# Schematic_drone.net
KiCad netlist of a schematic drawn in EasyEDA
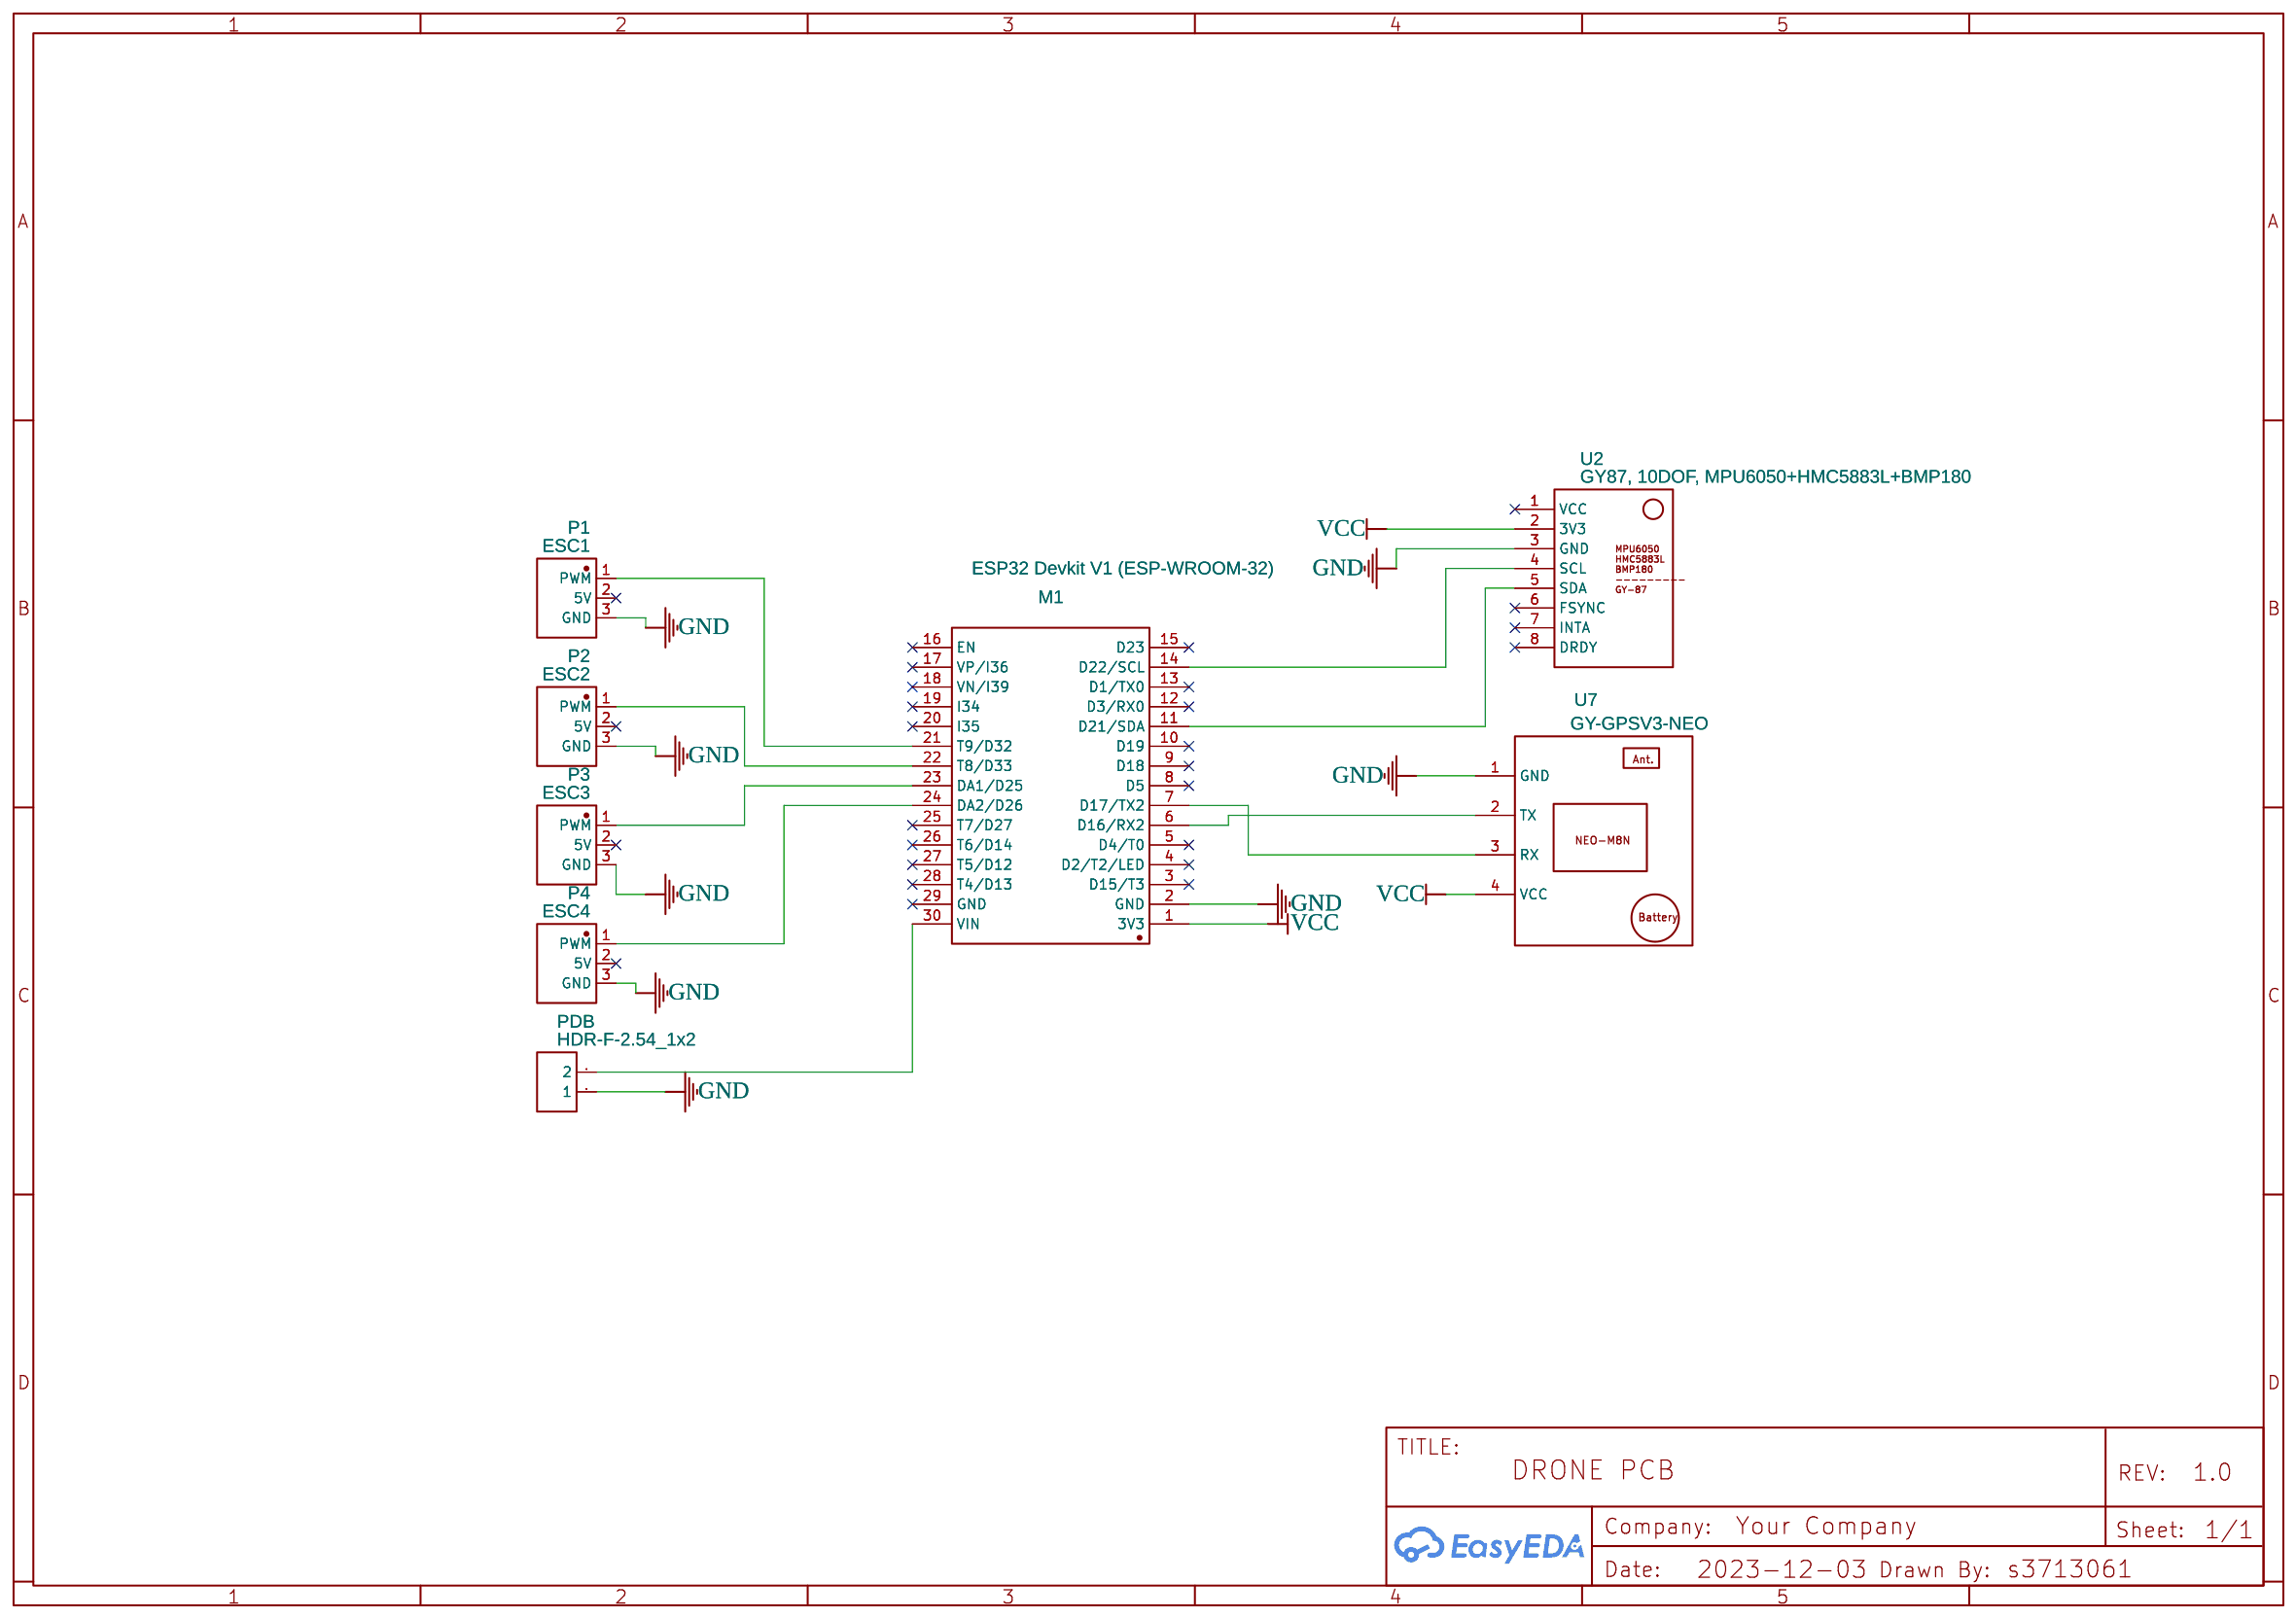
[diagram p0: schematic sheet]

(export (version "E")
  (design (tool "Eeschema 10.0.6"))
  (components
    (comp (ref "M1")
      (value "ESP32 Devkit V1 (ESP-WROOM-32)")
      (libsource (lib "") (part "S.Mod.ESP32_DOIT_V1 copy"))
    )
    (comp (ref "P1")
      (value "ESC1")
      (fields (field (name "Manufacturer") "Header2.54mm"))
      (libsource (lib "") (part "ESCPort"))
    )
    (comp (ref "P2")
      (value "ESC2")
      (fields (field (name "Manufacturer") "Header2.54mm"))
      (libsource (lib "") (part "ESCPort"))
    )
    (comp (ref "P3")
      (value "ESC3")
      (fields (field (name "Manufacturer") "Header2.54mm"))
      (libsource (lib "") (part "ESCPort"))
    )
    (comp (ref "P4")
      (value "ESC4")
      (fields (field (name "Manufacturer") "Header2.54mm"))
      (libsource (lib "") (part "ESCPort"))
    )
    (comp (ref "PDB")
      (value "HDR-F-2.54_1x2")
      (fields (field (name "Manufacturer") "Header2.54mm"))
      (libsource (lib "") (part "HDR-F-2.54_1x2"))
    )
    (comp (ref "U2")
      (value "GY87, 10DOF, MPU6050+HMC5883L+BMP180")
      (libsource (lib "") (part "GY87, 10DOF, MPU6050+HMC5883L+BMP180"))
    )
    (comp (ref "U7") (value "GY-GPSV3-NEO") (libsource (lib "") (part "GY-GPSV3-NEO COPY COPY")))
  )
  (nets
    (net (code "1") (name "GND") (class "Default")
      (node (ref "M1") (pin "2") (pinfunction "GND_2") (pintype "passive"))
      (node (ref "P1") (pin "3") (pinfunction "GND_3") (pintype "unspecified"))
      (node (ref "P2") (pin "3") (pinfunction "GND_3") (pintype "unspecified"))
      (node (ref "P3") (pin "3") (pinfunction "GND_3") (pintype "unspecified"))
      (node (ref "P4") (pin "3") (pinfunction "GND_3") (pintype "unspecified"))
      (node (ref "PDB") (pin "1") (pinfunction "1_1") (pintype "input"))
      (node (ref "U2") (pin "3") (pinfunction "GND_3") (pintype "unspecified"))
      (node (ref "U7") (pin "1") (pinfunction "GND_1") (pintype "unspecified"))
    )
    (net (code "2") (name "Net-(M1-D16{slash}RX2)") (class "Default")
      (node (ref "M1") (pin "6") (pinfunction "D16/RX2_6") (pintype "unspecified"))
      (node (ref "U7") (pin "2") (pinfunction "TX_2") (pintype "unspecified"))
    )
    (net (code "3") (name "Net-(M1-D17{slash}TX2)") (class "Default")
      (node (ref "M1") (pin "7") (pinfunction "D17/TX2_7") (pintype "unspecified"))
      (node (ref "U7") (pin "3") (pinfunction "RX_3") (pintype "unspecified"))
    )
    (net (code "4") (name "Net-(M1-D21{slash}SDA)") (class "Default")
      (node (ref "M1") (pin "11") (pinfunction "D21/SDA_11") (pintype "unspecified"))
      (node (ref "U2") (pin "5") (pinfunction "SDA_5") (pintype "unspecified"))
    )
    (net (code "5") (name "Net-(M1-D22{slash}SCL)") (class "Default")
      (node (ref "M1") (pin "14") (pinfunction "D22/SCL_14") (pintype "unspecified"))
      (node (ref "U2") (pin "4") (pinfunction "SCL_4") (pintype "unspecified"))
    )
    (net (code "6") (name "Net-(M1-DA1{slash}D25)") (class "Default")
      (node (ref "M1") (pin "23") (pinfunction "DA1/D25_23") (pintype "unspecified"))
      (node (ref "P3") (pin "1") (pinfunction "PWM_1") (pintype "unspecified"))
    )
    (net (code "7") (name "Net-(M1-DA2{slash}D26)") (class "Default")
      (node (ref "M1") (pin "24") (pinfunction "DA2/D26_24") (pintype "unspecified"))
      (node (ref "P4") (pin "1") (pinfunction "PWM_1") (pintype "unspecified"))
    )
    (net (code "8") (name "Net-(M1-T8{slash}D33)") (class "Default")
      (node (ref "M1") (pin "22") (pinfunction "T8/D33_22") (pintype "unspecified"))
      (node (ref "P2") (pin "1") (pinfunction "PWM_1") (pintype "unspecified"))
    )
    (net (code "9") (name "Net-(M1-T9{slash}D32)") (class "Default")
      (node (ref "M1") (pin "21") (pinfunction "T9/D32_21") (pintype "unspecified"))
      (node (ref "P1") (pin "1") (pinfunction "PWM_1") (pintype "unspecified"))
    )
    (net (code "10") (name "Net-(M1-VIN)") (class "Default")
      (node (ref "M1") (pin "30") (pinfunction "VIN_30") (pintype "passive"))
      (node (ref "PDB") (pin "2") (pinfunction "2_2") (pintype "input"))
    )
    (net (code "11") (name "VCC") (class "Default")
      (node (ref "M1") (pin "1") (pinfunction "3V3_1") (pintype "passive"))
      (node (ref "U2") (pin "2") (pinfunction "3V3_2") (pintype "unspecified"))
      (node (ref "U7") (pin "4") (pinfunction "VCC_4") (pintype "unspecified"))
    )
    (net (code "12") (name "unconnected-(M1-D1{slash}TX0-Pad13)") (class "Default")
      (node (ref "M1") (pin "13") (pinfunction "D1/TX0_13") (pintype "unspecified+no_connect"))
    )
    (net (code "13") (name "unconnected-(M1-D2{slash}T2{slash}LED-Pad4)") (class "Default")
      (node (ref "M1") (pin "4") (pinfunction "D2/T2/LED_4") (pintype "unspecified+no_connect"))
    )
    (net (code "14") (name "unconnected-(M1-D3{slash}RX0-Pad12)") (class "Default")
      (node (ref "M1") (pin "12") (pinfunction "D3/RX0_12") (pintype "unspecified+no_connect"))
    )
    (net (code "15") (name "unconnected-(M1-D4{slash}T0-Pad5)") (class "Default")
      (node (ref "M1") (pin "5") (pinfunction "D4/T0_5") (pintype "unspecified+no_connect"))
    )
    (net (code "16") (name "unconnected-(M1-D5-Pad8)") (class "Default")
      (node (ref "M1") (pin "8") (pinfunction "D5_8") (pintype "unspecified+no_connect"))
    )
    (net (code "17") (name "unconnected-(M1-D15{slash}T3-Pad3)") (class "Default")
      (node (ref "M1") (pin "3") (pinfunction "D15/T3_3") (pintype "unspecified+no_connect"))
    )
    (net (code "18") (name "unconnected-(M1-D18-Pad9)") (class "Default")
      (node (ref "M1") (pin "9") (pinfunction "D18_9") (pintype "unspecified+no_connect"))
    )
    (net (code "19") (name "unconnected-(M1-D19-Pad10)") (class "Default")
      (node (ref "M1") (pin "10") (pinfunction "D19_10") (pintype "unspecified+no_connect"))
    )
    (net (code "20") (name "unconnected-(M1-D23-Pad15)") (class "Default")
      (node (ref "M1") (pin "15") (pinfunction "D23_15") (pintype "unspecified+no_connect"))
    )
    (net (code "21") (name "unconnected-(M1-EN-Pad16)") (class "Default")
      (node (ref "M1") (pin "16") (pinfunction "EN_16") (pintype "unspecified+no_connect"))
    )
    (net (code "22") (name "unconnected-(M1-GND-Pad29)") (class "Default")
      (node (ref "M1") (pin "29") (pinfunction "GND_29") (pintype "passive+no_connect"))
    )
    (net (code "23") (name "unconnected-(M1-I34-Pad19)") (class "Default")
      (node (ref "M1") (pin "19") (pinfunction "I34_19") (pintype "input+no_connect"))
    )
    (net (code "24") (name "unconnected-(M1-I35-Pad20)") (class "Default")
      (node (ref "M1") (pin "20") (pinfunction "I35_20") (pintype "input+no_connect"))
    )
    (net (code "25") (name "unconnected-(M1-T4{slash}D13-Pad28)") (class "Default")
      (node (ref "M1") (pin "28") (pinfunction "T4/D13_28") (pintype "unspecified+no_connect"))
    )
    (net (code "26") (name "unconnected-(M1-T5{slash}D12-Pad27)") (class "Default")
      (node (ref "M1") (pin "27") (pinfunction "T5/D12_27") (pintype "unspecified+no_connect"))
    )
    (net (code "27") (name "unconnected-(M1-T6{slash}D14-Pad26)") (class "Default")
      (node (ref "M1") (pin "26") (pinfunction "T6/D14_26") (pintype "unspecified+no_connect"))
    )
    (net (code "28") (name "unconnected-(M1-T7{slash}D27-Pad25)") (class "Default")
      (node (ref "M1") (pin "25") (pinfunction "T7/D27_25") (pintype "unspecified+no_connect"))
    )
    (net (code "29") (name "unconnected-(M1-VN{slash}I39-Pad18)") (class "Default")
      (node (ref "M1") (pin "18") (pinfunction "VN/I39_18") (pintype "input+no_connect"))
    )
    (net (code "30") (name "unconnected-(M1-VP{slash}I36-Pad17)") (class "Default")
      (node (ref "M1") (pin "17") (pinfunction "VP/I36_17") (pintype "input+no_connect"))
    )
    (net (code "31") (name "unconnected-(P1-5V-Pad2)") (class "Default")
      (node (ref "P1") (pin "2") (pinfunction "5V_2") (pintype "unspecified+no_connect"))
    )
    (net (code "32") (name "unconnected-(P2-5V-Pad2)") (class "Default")
      (node (ref "P2") (pin "2") (pinfunction "5V_2") (pintype "unspecified+no_connect"))
    )
    (net (code "33") (name "unconnected-(P3-5V-Pad2)") (class "Default")
      (node (ref "P3") (pin "2") (pinfunction "5V_2") (pintype "unspecified+no_connect"))
    )
    (net (code "34") (name "unconnected-(P4-5V-Pad2)") (class "Default")
      (node (ref "P4") (pin "2") (pinfunction "5V_2") (pintype "unspecified+no_connect"))
    )
    (net (code "35") (name "unconnected-(U2-DRDY-Pad8)") (class "Default")
      (node (ref "U2") (pin "8") (pinfunction "DRDY_8") (pintype "unspecified+no_connect"))
    )
    (net (code "36") (name "unconnected-(U2-FSYNC-Pad6)") (class "Default")
      (node (ref "U2") (pin "6") (pinfunction "FSYNC_6") (pintype "unspecified+no_connect"))
    )
    (net (code "37") (name "unconnected-(U2-INTA-Pad7)") (class "Default")
      (node (ref "U2") (pin "7") (pinfunction "INTA_7") (pintype "unspecified+no_connect"))
    )
    (net (code "38") (name "unconnected-(U2-VCC-Pad1)") (class "Default")
      (node (ref "U2") (pin "1") (pinfunction "VCC_1") (pintype "unspecified+no_connect"))
    )
  )
)
